# ECG_PROJECT.net
KiCad netlist of a schematic drawn in EAGLE
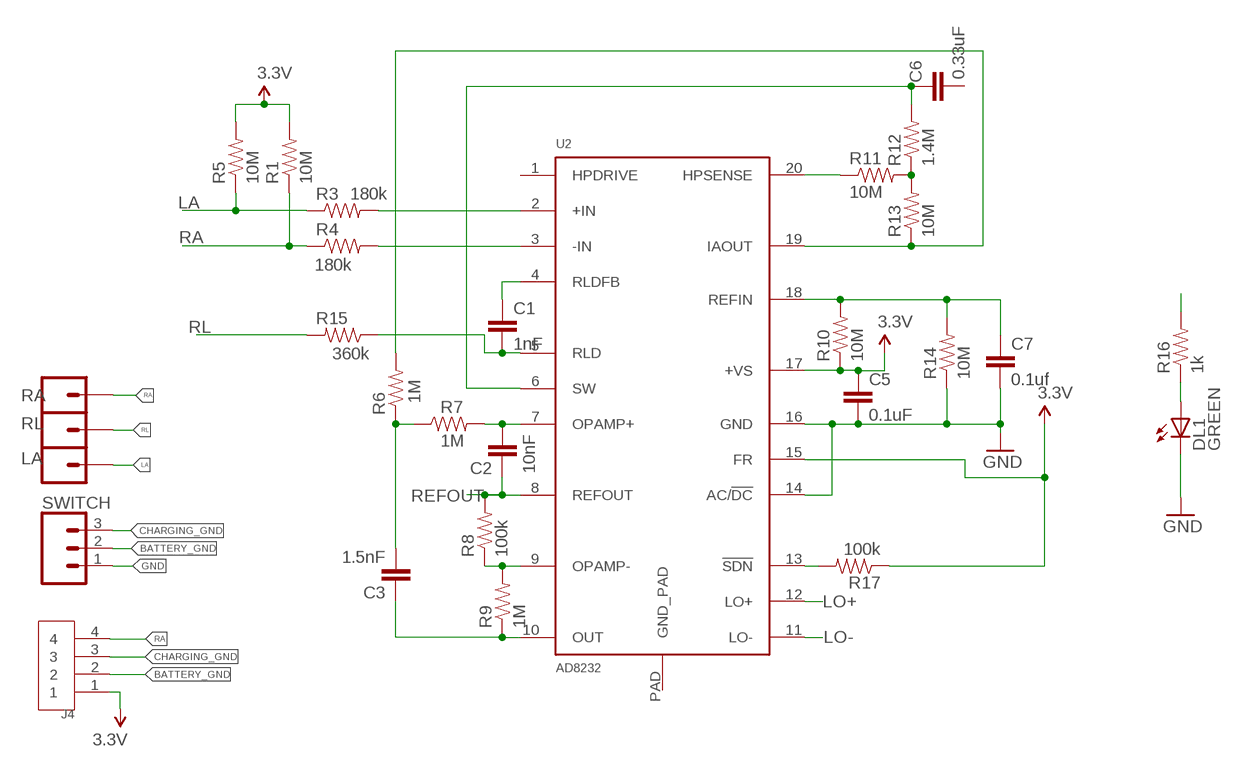
[diagram p0: schematic, sheet 1]
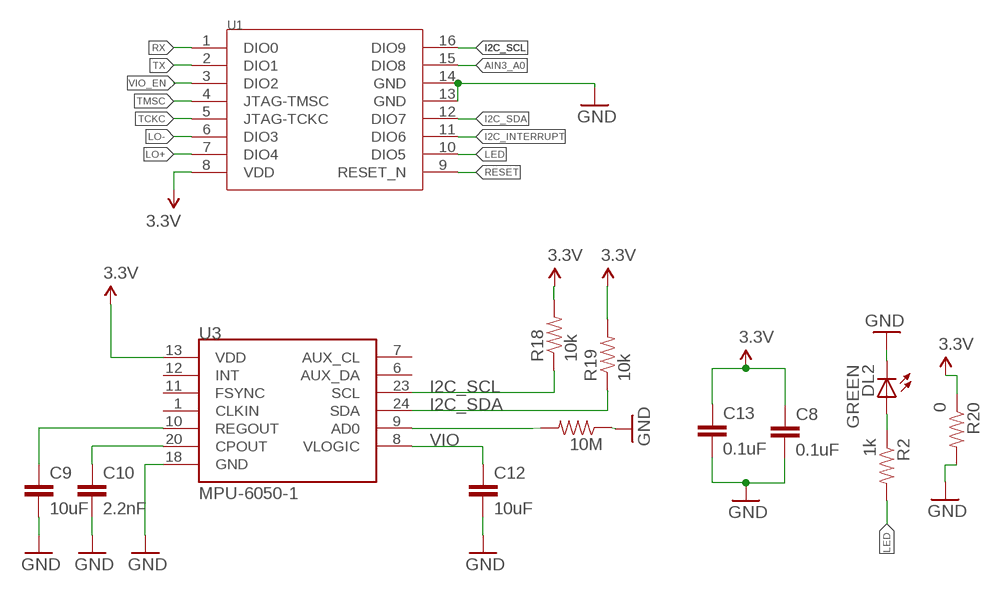
[diagram p1: schematic, sheet 2]

(export (version "E")
  (design (tool "Eeschema 10.0.6"))
  (components
    (comp (ref "10M")
      (value "1k")
      (footprint "eagle-import:0603-RES")
      (libsource (lib "eagle-import") (part "1K-1%"))
    )
    (comp (ref "C8")
      (value "0.1uF")
      (footprint "eagle-import:0603-CAP")
      (libsource (lib "eagle-import") (part "CAP0603-CAP"))
    )
    (comp (ref "C9")
      (value "10uF")
      (footprint "eagle-import:0603-CAP")
      (libsource (lib "eagle-import") (part "CAP0603-CAP"))
    )
    (comp (ref "C10")
      (value "2.2nF")
      (footprint "eagle-import:0603-CAP")
      (libsource (lib "eagle-import") (part "CAP0603-CAP"))
    )
    (comp (ref "C12")
      (value "10uF")
      (footprint "eagle-import:0603-CAP")
      (libsource (lib "eagle-import") (part "CAP0603-CAP"))
    )
    (comp (ref "C13")
      (value "0.1uF")
      (footprint "eagle-import:0603-CAP")
      (libsource (lib "eagle-import") (part "CAP0603-CAP"))
    )
    (comp (ref "DL2")
      (value "GREEN")
      (footprint "eagle-import:LEDC1608X80N-AK")
      (fields (field (name "MANUFACTURER") "Avago "))
      (libsource (lib "eagle-import") (part "LED-0603-GREEN"))
    )
    (comp (ref "R2")
      (value "1k")
      (footprint "eagle-import:0603-RES")
      (libsource (lib "eagle-import") (part "1K-1%"))
    )
    (comp (ref "R18")
      (value "10k")
      (footprint "eagle-import:0603-RES")
      (libsource (lib "eagle-import") (part "RESISTOR0603-RES"))
    )
    (comp (ref "R19")
      (value "10k")
      (footprint "eagle-import:0603-RES")
      (libsource (lib "eagle-import") (part "RESISTOR0603-RES"))
    )
    (comp (ref "R20")
      (value "0")
      (footprint "eagle-import:0603-RES")
      (libsource (lib "eagle-import") (part "RESISTOR0603-RES"))
    )
    (comp (ref "U1")
      (value "IC-MCU-5.1GHZ-CANSECIC-MCU-5.1GHZ-CANSEC_AN2640R2SA-K_MODULE$20$-$20$DUPLICATE")
      (footprint "eagle-import:AN2640R2SA-K_MODULE$20$-$20$DUPLICATE")
      (fields
        (field (name "MFG") "CANSEC")
        (field (name "ENGINEER_CREATED") "SL")
        (field (name "OWNER") "OoB Services")
      )
      (libsource (lib "eagle-import") (part "IC-MCU-5.1GHZ-CANSECIC-MCU-5.1GHZ-CANSEC_AN2640R2SA-K_MODULE$20$-$20$DUPLICATE"))
    )
    (comp (ref "U3")
      (value "MPU-6050-1")
      (footprint "eagle-import:QFN-24-4MM2")
      (libsource (lib "eagle-import") (part "MPU-6050-1"))
    )
    (comp (ref "C1")
      (value "1nF")
      (footprint "eagle-import:0603-CAP")
      (libsource (lib "eagle-import") (part "SparkFun-Passives_CAP0603-CAP"))
    )
    (comp (ref "C2")
      (value "10nF")
      (footprint "eagle-import:0603-CAP")
      (libsource (lib "eagle-import") (part "SparkFun-Passives_CAP0603-CAP"))
    )
    (comp (ref "C3")
      (value "1.5nF")
      (footprint "eagle-import:0603-CAP")
      (libsource (lib "eagle-import") (part "SparkFun-Passives_CAP0603-CAP"))
    )
    (comp (ref "C5")
      (value "0.1uF")
      (footprint "eagle-import:0603-CAP")
      (libsource (lib "eagle-import") (part "SparkFun-Passives_CAP0603-CAP"))
    )
    (comp (ref "C6")
      (value "0.33uF")
      (footprint "eagle-import:0603-CAP")
      (libsource (lib "eagle-import") (part "SparkFun-Passives_CAP0603-CAP"))
    )
    (comp (ref "C7")
      (value "0.1uf")
      (footprint "eagle-import:0603-CAP")
      (libsource (lib "eagle-import") (part "SparkFun-Passives_CAP0603-CAP"))
    )
    (comp (ref "DL1")
      (value "GREEN")
      (footprint "eagle-import:LEDC1608X80N-AK")
      (fields (field (name "MANUFACTURER") "Avago "))
      (libsource (lib "eagle-import") (part "LED-0603-GREEN"))
    )
    (comp (ref "J4")
      (value "CON-FPC-1MM-04-TE$20$CONNECTIVITY$20$AMP$20$CONNECTORSCON-FPC-1MM-04-TE$20$CONNECTIVITY$20$AMP$20$CONNECTORS_FPC-4PIN")
      (footprint "eagle-import:FPC-4PIN")
      (fields (field (name "MFG") "TE Connectivity AMP Connectors") (field (name "ENGINEER_CREATED") "SL"))
      (libsource (lib "eagle-import") (part "CON-FPC-1MM-04-TE$20$CONNECTIVITY$20$AMP$20$CONNECTORSCON-FPC-1MM-04-TE$20$CONNECTIVITY$20$AMP$20$CONNECTORS_FPC-4PIN"))
    )
    (comp (ref "LA")
      (value "CONN_01")
      (footprint "eagle-import:1X01")
      (libsource (lib "eagle-import") (part "CONN_01"))
    )
    (comp (ref "R1")
      (value "10M")
      (footprint "eagle-import:0603-RES")
      (libsource (lib "eagle-import") (part "SparkFun-Passives_RESISTOR0603-RES"))
    )
    (comp (ref "R3")
      (value "180k")
      (footprint "eagle-import:0603-RES")
      (libsource (lib "eagle-import") (part "SparkFun-Passives_RESISTOR0603-RES"))
    )
    (comp (ref "R4")
      (value "180k")
      (footprint "eagle-import:0603-RES")
      (libsource (lib "eagle-import") (part "SparkFun-Passives_RESISTOR0603-RES"))
    )
    (comp (ref "R5")
      (value "10M")
      (footprint "eagle-import:0603-RES")
      (libsource (lib "eagle-import") (part "SparkFun-Passives_RESISTOR0603-RES"))
    )
    (comp (ref "R6")
      (value "1M")
      (footprint "eagle-import:0603-RES")
      (libsource (lib "eagle-import") (part "SparkFun-Passives_RESISTOR0603-RES"))
    )
    (comp (ref "R7")
      (value "1M")
      (footprint "eagle-import:0603-RES")
      (libsource (lib "eagle-import") (part "SparkFun-Passives_RESISTOR0603-RES"))
    )
    (comp (ref "R8")
      (value "100k")
      (footprint "eagle-import:0603-RES")
      (libsource (lib "eagle-import") (part "SparkFun-Passives_RESISTOR0603-RES"))
    )
    (comp (ref "R9")
      (value "1M")
      (footprint "eagle-import:0603-RES")
      (libsource (lib "eagle-import") (part "SparkFun-Passives_RESISTOR0603-RES"))
    )
    (comp (ref "R10")
      (value "10M")
      (footprint "eagle-import:0603-RES")
      (libsource (lib "eagle-import") (part "SparkFun-Passives_RESISTOR0603-RES"))
    )
    (comp (ref "R11")
      (value "10M")
      (footprint "eagle-import:0603-RES")
      (libsource (lib "eagle-import") (part "SparkFun-Passives_RESISTOR0603-RES"))
    )
    (comp (ref "R12")
      (value "1.4M")
      (footprint "eagle-import:0603-RES")
      (libsource (lib "eagle-import") (part "SparkFun-Passives_RESISTOR0603-RES"))
    )
    (comp (ref "R13")
      (value "10M")
      (footprint "eagle-import:0603-RES")
      (libsource (lib "eagle-import") (part "SparkFun-Passives_RESISTOR0603-RES"))
    )
    (comp (ref "R14")
      (value "10M")
      (footprint "eagle-import:0603-RES")
      (libsource (lib "eagle-import") (part "SparkFun-Passives_RESISTOR0603-RES"))
    )
    (comp (ref "R15")
      (value "360k")
      (footprint "eagle-import:0603-RES")
      (libsource (lib "eagle-import") (part "SparkFun-Passives_RESISTOR0603-RES"))
    )
    (comp (ref "R16")
      (value "1k")
      (footprint "eagle-import:0603-RES")
      (libsource (lib "eagle-import") (part "1K-1%"))
    )
    (comp (ref "R17")
      (value "100k")
      (footprint "eagle-import:0603-RES")
      (libsource (lib "eagle-import") (part "1K-1%"))
    )
    (comp (ref "RA")
      (value "CONN_01")
      (footprint "eagle-import:1X01")
      (libsource (lib "eagle-import") (part "CONN_01"))
    )
    (comp (ref "RL")
      (value "CONN_01")
      (footprint "eagle-import:1X01")
      (libsource (lib "eagle-import") (part "CONN_01"))
    )
    (comp (ref "SWITCH")
      (value "455-1750-1-ND")
      (footprint "eagle-import:1X03")
      (libsource (lib "eagle-import") (part "CONN_03"))
    )
    (comp (ref "U2")
      (value "AD8232")
      (footprint "eagle-import:LFCSP_20")
      (libsource (lib "eagle-import") (part "AD8232"))
    )
  )
  (nets
    (net (code "1") (name "3.3V") (class "Default")
      (node (ref "C13") (pin "1") (pinfunction "1_1") (pintype "passive"))
      (node (ref "C5") (pin "1") (pinfunction "1_1") (pintype "passive"))
      (node (ref "C8") (pin "1") (pinfunction "1_1") (pintype "passive"))
      (node (ref "J4") (pin "1") (pinfunction "1_1") (pintype "power_in"))
      (node (ref "R1") (pin "2") (pinfunction "2_2") (pintype "passive"))
      (node (ref "R10") (pin "1") (pinfunction "1_1") (pintype "passive"))
      (node (ref "R17") (pin "1") (pinfunction "1_1") (pintype "passive"))
      (node (ref "R18") (pin "2") (pinfunction "2_2") (pintype "passive"))
      (node (ref "R19") (pin "2") (pinfunction "2_2") (pintype "passive"))
      (node (ref "R20") (pin "1") (pinfunction "1_1") (pintype "passive"))
      (node (ref "R5") (pin "2") (pinfunction "2_2") (pintype "passive"))
      (node (ref "U1") (pin "8") (pinfunction "VDD_8") (pintype "passive"))
      (node (ref "U2") (pin "15") (pinfunction "FR_15") (pintype "bidirectional"))
      (node (ref "U2") (pin "17") (pinfunction "+VS_17") (pintype "bidirectional"))
      (node (ref "U3") (pin "13") (pinfunction "VDD_13") (pintype "bidirectional"))
    )
    (net (code "2") (name "AIN3_A0") (class "Default")
      (node (ref "C3") (pin "1") (pinfunction "1_1") (pintype "passive"))
      (node (ref "R16") (pin "2") (pinfunction "2_2") (pintype "passive"))
      (node (ref "R9") (pin "1") (pinfunction "1_1") (pintype "passive"))
      (node (ref "U1") (pin "15") (pinfunction "DIO8_15") (pintype "passive"))
      (node (ref "U2") (pin "10") (pinfunction "OUT_10") (pintype "bidirectional"))
    )
    (net (code "3") (name "BATTERY_GND") (class "Default")
      (node (ref "J4") (pin "2") (pinfunction "2_2") (pintype "passive"))
      (node (ref "SWITCH") (pin "2") (pinfunction "2_2") (pintype "passive"))
    )
    (net (code "4") (name "CHARGING_GND") (class "Default")
      (node (ref "J4") (pin "3") (pinfunction "3_3") (pintype "passive"))
      (node (ref "SWITCH") (pin "3") (pinfunction "3_3") (pintype "passive"))
    )
    (net (code "5") (name "GND") (class "Default")
      (node (ref "10M") (pin "1") (pinfunction "1_1") (pintype "passive"))
      (node (ref "C10") (pin "2") (pinfunction "2_2") (pintype "passive"))
      (node (ref "C12") (pin "2") (pinfunction "2_2") (pintype "passive"))
      (node (ref "C13") (pin "2") (pinfunction "2_2") (pintype "passive"))
      (node (ref "C5") (pin "2") (pinfunction "2_2") (pintype "passive"))
      (node (ref "C7") (pin "2") (pinfunction "2_2") (pintype "passive"))
      (node (ref "C8") (pin "2") (pinfunction "2_2") (pintype "passive"))
      (node (ref "C9") (pin "2") (pinfunction "2_2") (pintype "passive"))
      (node (ref "DL1") (pin "C") (pinfunction "C_C") (pintype "passive"))
      (node (ref "DL2") (pin "C") (pinfunction "C_C") (pintype "passive"))
      (node (ref "R14") (pin "1") (pinfunction "1_1") (pintype "passive"))
      (node (ref "R20") (pin "2") (pinfunction "2_2") (pintype "passive"))
      (node (ref "SWITCH") (pin "1") (pinfunction "1_1") (pintype "passive"))
      (node (ref "U1") (pin "13") (pinfunction "GND_13") (pintype "passive"))
      (node (ref "U1") (pin "14") (pinfunction "GND_14") (pintype "passive"))
      (node (ref "U2") (pin "14") (pinfunction "AC/~{DC}_14") (pintype "bidirectional"))
      (node (ref "U2") (pin "16") (pinfunction "GND_16") (pintype "bidirectional"))
      (node (ref "U3") (pin "18") (pinfunction "GND_18") (pintype "bidirectional"))
    )
    (net (code "6") (name "I2C_INTERRUPT") (class "Default")
      (node (ref "U1") (pin "11") (pinfunction "DIO6_11") (pintype "passive"))
    )
    (net (code "7") (name "I2C_SCL") (class "Default")
      (node (ref "R18") (pin "1") (pinfunction "1_1") (pintype "passive"))
      (node (ref "U1") (pin "16") (pinfunction "DIO9_16") (pintype "passive"))
      (node (ref "U3") (pin "23") (pinfunction "SCL_23") (pintype "bidirectional"))
    )
    (net (code "8") (name "I2C_SDA") (class "Default")
      (node (ref "R19") (pin "1") (pinfunction "1_1") (pintype "passive"))
      (node (ref "U1") (pin "12") (pinfunction "DIO7_12") (pintype "passive"))
      (node (ref "U3") (pin "24") (pinfunction "SDA_24") (pintype "bidirectional"))
    )
    (net (code "9") (name "LA") (class "Default")
      (node (ref "LA") (pin "1") (pinfunction "1_1") (pintype "passive"))
      (node (ref "R3") (pin "1") (pinfunction "1_1") (pintype "passive"))
      (node (ref "R5") (pin "1") (pinfunction "1_1") (pintype "passive"))
    )
    (net (code "10") (name "LED") (class "Default")
      (node (ref "R2") (pin "2") (pinfunction "2_2") (pintype "passive"))
      (node (ref "U1") (pin "10") (pinfunction "DIO5_10") (pintype "passive"))
    )
    (net (code "11") (name "LO+") (class "Default")
      (node (ref "U1") (pin "7") (pinfunction "DIO4_7") (pintype "passive"))
      (node (ref "U2") (pin "12") (pinfunction "LO+_12") (pintype "bidirectional"))
    )
    (net (code "12") (name "LO-") (class "Default")
      (node (ref "U1") (pin "6") (pinfunction "DIO3_6") (pintype "passive"))
      (node (ref "U2") (pin "11") (pinfunction "LO-_11") (pintype "bidirectional"))
    )
    (net (code "13") (name "Net-(C3-Pad2)") (class "Default")
      (node (ref "C3") (pin "2") (pinfunction "2_2") (pintype "passive"))
      (node (ref "R6") (pin "1") (pinfunction "1_1") (pintype "passive"))
      (node (ref "R7") (pin "1") (pinfunction "1_1") (pintype "passive"))
    )
    (net (code "14") (name "Net-(DL1-PadA)") (class "Default")
      (node (ref "DL1") (pin "A") (pinfunction "A_A") (pintype "passive"))
      (node (ref "R16") (pin "1") (pinfunction "1_1") (pintype "passive"))
    )
    (net (code "15") (name "Net-(DL2-PadA)") (class "Default")
      (node (ref "DL2") (pin "A") (pinfunction "A_A") (pintype "passive"))
      (node (ref "R2") (pin "1") (pinfunction "1_1") (pintype "passive"))
    )
    (net (code "16") (name "Net-(R11-Pad2)") (class "Default")
      (node (ref "R11") (pin "2") (pinfunction "2_2") (pintype "passive"))
      (node (ref "R12") (pin "1") (pinfunction "1_1") (pintype "passive"))
      (node (ref "R13") (pin "2") (pinfunction "2_2") (pintype "passive"))
    )
    (net (code "17") (name "Net-(U2-+IN)") (class "Default")
      (node (ref "R3") (pin "2") (pinfunction "2_2") (pintype "passive"))
      (node (ref "U2") (pin "2") (pinfunction "+IN_2") (pintype "bidirectional"))
    )
    (net (code "18") (name "Net-(U2--IN)") (class "Default")
      (node (ref "R4") (pin "2") (pinfunction "2_2") (pintype "passive"))
      (node (ref "U2") (pin "3") (pinfunction "-IN_3") (pintype "bidirectional"))
    )
    (net (code "19") (name "Net-(U2-HPSENSE)") (class "Default")
      (node (ref "R11") (pin "1") (pinfunction "1_1") (pintype "passive"))
      (node (ref "U2") (pin "20") (pinfunction "HPSENSE_20") (pintype "bidirectional"))
    )
    (net (code "20") (name "Net-(U2-IAOUT)") (class "Default")
      (node (ref "R13") (pin "1") (pinfunction "1_1") (pintype "passive"))
      (node (ref "R6") (pin "2") (pinfunction "2_2") (pintype "passive"))
      (node (ref "U2") (pin "19") (pinfunction "IAOUT_19") (pintype "bidirectional"))
    )
    (net (code "21") (name "Net-(U2-OPAMP+)") (class "Default")
      (node (ref "C2") (pin "2") (pinfunction "2_2") (pintype "passive"))
      (node (ref "R7") (pin "2") (pinfunction "2_2") (pintype "passive"))
      (node (ref "U2") (pin "7") (pinfunction "OPAMP+_7") (pintype "bidirectional"))
    )
    (net (code "22") (name "Net-(U2-OPAMP-)") (class "Default")
      (node (ref "R8") (pin "1") (pinfunction "1_1") (pintype "passive"))
      (node (ref "R9") (pin "2") (pinfunction "2_2") (pintype "passive"))
      (node (ref "U2") (pin "9") (pinfunction "OPAMP-_9") (pintype "bidirectional"))
    )
    (net (code "23") (name "Net-(U2-REFIN)") (class "Default")
      (node (ref "C7") (pin "1") (pinfunction "1_1") (pintype "passive"))
      (node (ref "R10") (pin "2") (pinfunction "2_2") (pintype "passive"))
      (node (ref "R14") (pin "2") (pinfunction "2_2") (pintype "passive"))
      (node (ref "U2") (pin "18") (pinfunction "REFIN_18") (pintype "bidirectional"))
    )
    (net (code "24") (name "Net-(U2-RLD)") (class "Default")
      (node (ref "C1") (pin "2") (pinfunction "2_2") (pintype "passive"))
      (node (ref "R15") (pin "1") (pinfunction "1_1") (pintype "passive"))
      (node (ref "U2") (pin "5") (pinfunction "RLD_5") (pintype "bidirectional"))
    )
    (net (code "25") (name "Net-(U2-RLDFB)") (class "Default")
      (node (ref "C1") (pin "1") (pinfunction "1_1") (pintype "passive"))
      (node (ref "U2") (pin "4") (pinfunction "RLDFB_4") (pintype "bidirectional"))
    )
    (net (code "26") (name "Net-(U2-SW)") (class "Default")
      (node (ref "C6") (pin "1") (pinfunction "1_1") (pintype "passive"))
      (node (ref "R12") (pin "2") (pinfunction "2_2") (pintype "passive"))
      (node (ref "U2") (pin "6") (pinfunction "SW_6") (pintype "bidirectional"))
    )
    (net (code "27") (name "Net-(U2-~{SDN})") (class "Default")
      (node (ref "R17") (pin "2") (pinfunction "2_2") (pintype "passive"))
      (node (ref "U2") (pin "13") (pinfunction "~{SDN}_13") (pintype "bidirectional"))
    )
    (net (code "28") (name "Net-(U3-AD0)") (class "Default")
      (node (ref "10M") (pin "2") (pinfunction "2_2") (pintype "passive"))
      (node (ref "U3") (pin "9") (pinfunction "AD0_9") (pintype "bidirectional"))
    )
    (net (code "29") (name "Net-(U3-CPOUT)") (class "Default")
      (node (ref "C10") (pin "1") (pinfunction "1_1") (pintype "passive"))
      (node (ref "U3") (pin "20") (pinfunction "CPOUT_20") (pintype "bidirectional"))
    )
    (net (code "30") (name "Net-(U3-REGOUT)") (class "Default")
      (node (ref "C9") (pin "1") (pinfunction "1_1") (pintype "passive"))
      (node (ref "U3") (pin "10") (pinfunction "REGOUT_10") (pintype "bidirectional"))
    )
    (net (code "31") (name "RA") (class "Default")
      (node (ref "J4") (pin "4") (pinfunction "4_4") (pintype "power_in"))
      (node (ref "R1") (pin "1") (pinfunction "1_1") (pintype "passive"))
      (node (ref "R4") (pin "1") (pinfunction "1_1") (pintype "passive"))
      (node (ref "RA") (pin "1") (pinfunction "1_1") (pintype "passive"))
    )
    (net (code "32") (name "REFOUT") (class "Default")
      (node (ref "C2") (pin "1") (pinfunction "1_1") (pintype "passive"))
      (node (ref "R8") (pin "2") (pinfunction "2_2") (pintype "passive"))
      (node (ref "U2") (pin "8") (pinfunction "REFOUT_8") (pintype "bidirectional"))
    )
    (net (code "33") (name "RESET") (class "Default")
      (node (ref "U1") (pin "9") (pinfunction "RESET_N_9") (pintype "passive"))
    )
    (net (code "34") (name "RL") (class "Default")
      (node (ref "R15") (pin "2") (pinfunction "2_2") (pintype "passive"))
      (node (ref "RL") (pin "1") (pinfunction "1_1") (pintype "passive"))
    )
    (net (code "35") (name "RX") (class "Default")
      (node (ref "U1") (pin "1") (pinfunction "DIO0_1") (pintype "passive"))
    )
    (net (code "36") (name "TCKC") (class "Default")
      (node (ref "U1") (pin "5") (pinfunction "JTAG-TCKC_5") (pintype "passive"))
    )
    (net (code "37") (name "TMSC") (class "Default")
      (node (ref "U1") (pin "4") (pinfunction "JTAG-TMSC_4") (pintype "passive"))
    )
    (net (code "38") (name "TX") (class "Default")
      (node (ref "U1") (pin "2") (pinfunction "DIO1_2") (pintype "passive"))
    )
    (net (code "39") (name "VIO") (class "Default")
      (node (ref "C12") (pin "1") (pinfunction "1_1") (pintype "passive"))
      (node (ref "U3") (pin "8") (pinfunction "VLOGIC_8") (pintype "bidirectional"))
    )
    (net (code "40") (name "VIO_EN") (class "Default")
      (node (ref "U1") (pin "3") (pinfunction "DIO2_3") (pintype "passive"))
    )
    (net (code "41") (name "unconnected-(C6-Pad2)") (class "Default")
      (node (ref "C6") (pin "2") (pinfunction "2_2") (pintype "passive"))
    )
    (net (code "42") (name "unconnected-(U2-GND_PAD-PadPAD)") (class "Default")
      (node (ref "U2") (pin "PAD") (pinfunction "GND_PAD_PAD") (pintype "bidirectional"))
    )
    (net (code "43") (name "unconnected-(U2-HPDRIVE-Pad1)") (class "Default")
      (node (ref "U2") (pin "1") (pinfunction "HPDRIVE_1") (pintype "bidirectional"))
    )
    (net (code "44") (name "unconnected-(U3-AUX_CL-Pad7)") (class "Default")
      (node (ref "U3") (pin "7") (pinfunction "AUX_CL_7") (pintype "bidirectional"))
    )
    (net (code "45") (name "unconnected-(U3-AUX_DA-Pad6)") (class "Default")
      (node (ref "U3") (pin "6") (pinfunction "AUX_DA_6") (pintype "bidirectional"))
    )
    (net (code "46") (name "unconnected-(U3-CLKIN-Pad1)") (class "Default")
      (node (ref "U3") (pin "1") (pinfunction "CLKIN_1") (pintype "bidirectional"))
    )
    (net (code "47") (name "unconnected-(U3-FSYNC-Pad11)") (class "Default")
      (node (ref "U3") (pin "11") (pinfunction "FSYNC_11") (pintype "bidirectional"))
    )
    (net (code "48") (name "unconnected-(U3-INT-Pad12)") (class "Default")
      (node (ref "U3") (pin "12") (pinfunction "INT_12") (pintype "bidirectional"))
    )
  )
)
